# extenstion-board.net
KiCad netlist of a schematic drawn in EAGLE
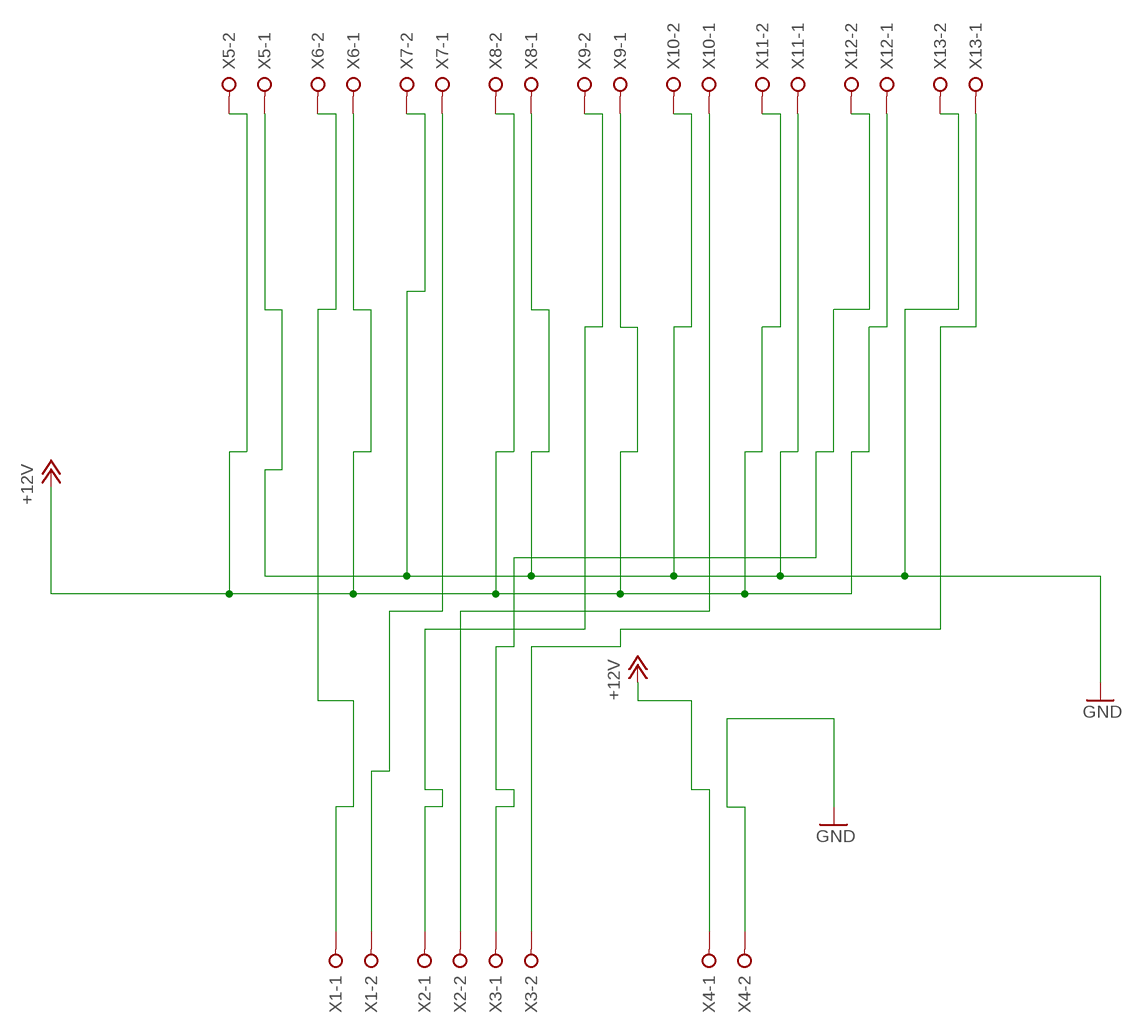
[diagram p0: schematic, sheet 1]

(export (version "E")
  (design (tool "Eeschema 10.0.6"))
  (components
    (comp (ref "X1")
      (value "W237-02P")
      (footprint "eagle-import:W237-132")
      (libsource (lib "eagle-import") (part "W237-02P"))
    )
    (comp (ref "X2")
      (value "W237-02P")
      (footprint "eagle-import:W237-132")
      (libsource (lib "eagle-import") (part "W237-02P"))
    )
    (comp (ref "X3")
      (value "W237-02P")
      (footprint "eagle-import:W237-132")
      (libsource (lib "eagle-import") (part "W237-02P"))
    )
    (comp (ref "X4")
      (value "W237-02P")
      (footprint "eagle-import:W237-132")
      (libsource (lib "eagle-import") (part "W237-02P"))
    )
    (comp (ref "X5")
      (value "W237-02P")
      (footprint "eagle-import:W237-132")
      (libsource (lib "eagle-import") (part "W237-02P"))
    )
    (comp (ref "X6")
      (value "W237-02P")
      (footprint "eagle-import:W237-132")
      (libsource (lib "eagle-import") (part "W237-02P"))
    )
    (comp (ref "X7")
      (value "W237-02P")
      (footprint "eagle-import:W237-132")
      (libsource (lib "eagle-import") (part "W237-02P"))
    )
    (comp (ref "X8")
      (value "W237-02P")
      (footprint "eagle-import:W237-132")
      (libsource (lib "eagle-import") (part "W237-02P"))
    )
    (comp (ref "X9")
      (value "W237-02P")
      (footprint "eagle-import:W237-132")
      (libsource (lib "eagle-import") (part "W237-02P"))
    )
    (comp (ref "X10")
      (value "W237-02P")
      (footprint "eagle-import:W237-132")
      (libsource (lib "eagle-import") (part "W237-02P"))
    )
    (comp (ref "X11")
      (value "W237-02P")
      (footprint "eagle-import:W237-132")
      (libsource (lib "eagle-import") (part "W237-02P"))
    )
    (comp (ref "X12")
      (value "W237-02P")
      (footprint "eagle-import:W237-132")
      (libsource (lib "eagle-import") (part "W237-02P"))
    )
    (comp (ref "X13")
      (value "W237-02P")
      (footprint "eagle-import:W237-132")
      (libsource (lib "eagle-import") (part "W237-02P"))
    )
  )
  (nets
    (net (code "1") (name "+12V") (class "Default")
      (node (ref "X11") (pin "2") (pinfunction "KL_2") (pintype "passive"))
      (node (ref "X12") (pin "1") (pinfunction "KL_1") (pintype "passive"))
      (node (ref "X4") (pin "1") (pinfunction "KL_1") (pintype "passive"))
      (node (ref "X5") (pin "2") (pinfunction "KL_2") (pintype "passive"))
      (node (ref "X6") (pin "1") (pinfunction "KL_1") (pintype "passive"))
      (node (ref "X8") (pin "2") (pinfunction "KL_2") (pintype "passive"))
      (node (ref "X9") (pin "1") (pinfunction "KL_1") (pintype "passive"))
    )
    (net (code "2") (name "GND") (class "Default")
      (node (ref "X10") (pin "2") (pinfunction "KL_2") (pintype "passive"))
      (node (ref "X11") (pin "1") (pinfunction "KL_1") (pintype "passive"))
      (node (ref "X13") (pin "2") (pinfunction "KL_2") (pintype "passive"))
      (node (ref "X4") (pin "2") (pinfunction "KL_2") (pintype "passive"))
      (node (ref "X5") (pin "1") (pinfunction "KL_1") (pintype "passive"))
      (node (ref "X7") (pin "2") (pinfunction "KL_2") (pintype "passive"))
      (node (ref "X8") (pin "1") (pinfunction "KL_1") (pintype "passive"))
    )
    (net (code "3") (name "Net-(X1A-KL)") (class "Default")
      (node (ref "X1") (pin "1") (pinfunction "KL_1") (pintype "passive"))
      (node (ref "X6") (pin "2") (pinfunction "KL_2") (pintype "passive"))
    )
    (net (code "4") (name "Net-(X1B-KL)") (class "Default")
      (node (ref "X1") (pin "2") (pinfunction "KL_2") (pintype "passive"))
      (node (ref "X7") (pin "1") (pinfunction "KL_1") (pintype "passive"))
    )
    (net (code "5") (name "Net-(X2A-KL)") (class "Default")
      (node (ref "X2") (pin "1") (pinfunction "KL_1") (pintype "passive"))
      (node (ref "X9") (pin "2") (pinfunction "KL_2") (pintype "passive"))
    )
    (net (code "6") (name "Net-(X10A-KL)") (class "Default")
      (node (ref "X10") (pin "1") (pinfunction "KL_1") (pintype "passive"))
      (node (ref "X2") (pin "2") (pinfunction "KL_2") (pintype "passive"))
    )
    (net (code "7") (name "Net-(X12B-KL)") (class "Default")
      (node (ref "X12") (pin "2") (pinfunction "KL_2") (pintype "passive"))
      (node (ref "X3") (pin "1") (pinfunction "KL_1") (pintype "passive"))
    )
    (net (code "8") (name "Net-(X13A-KL)") (class "Default")
      (node (ref "X13") (pin "1") (pinfunction "KL_1") (pintype "passive"))
      (node (ref "X3") (pin "2") (pinfunction "KL_2") (pintype "passive"))
    )
  )
)
